# Sheet1.net
KiCad netlist of a schematic drawn in Altium Designer
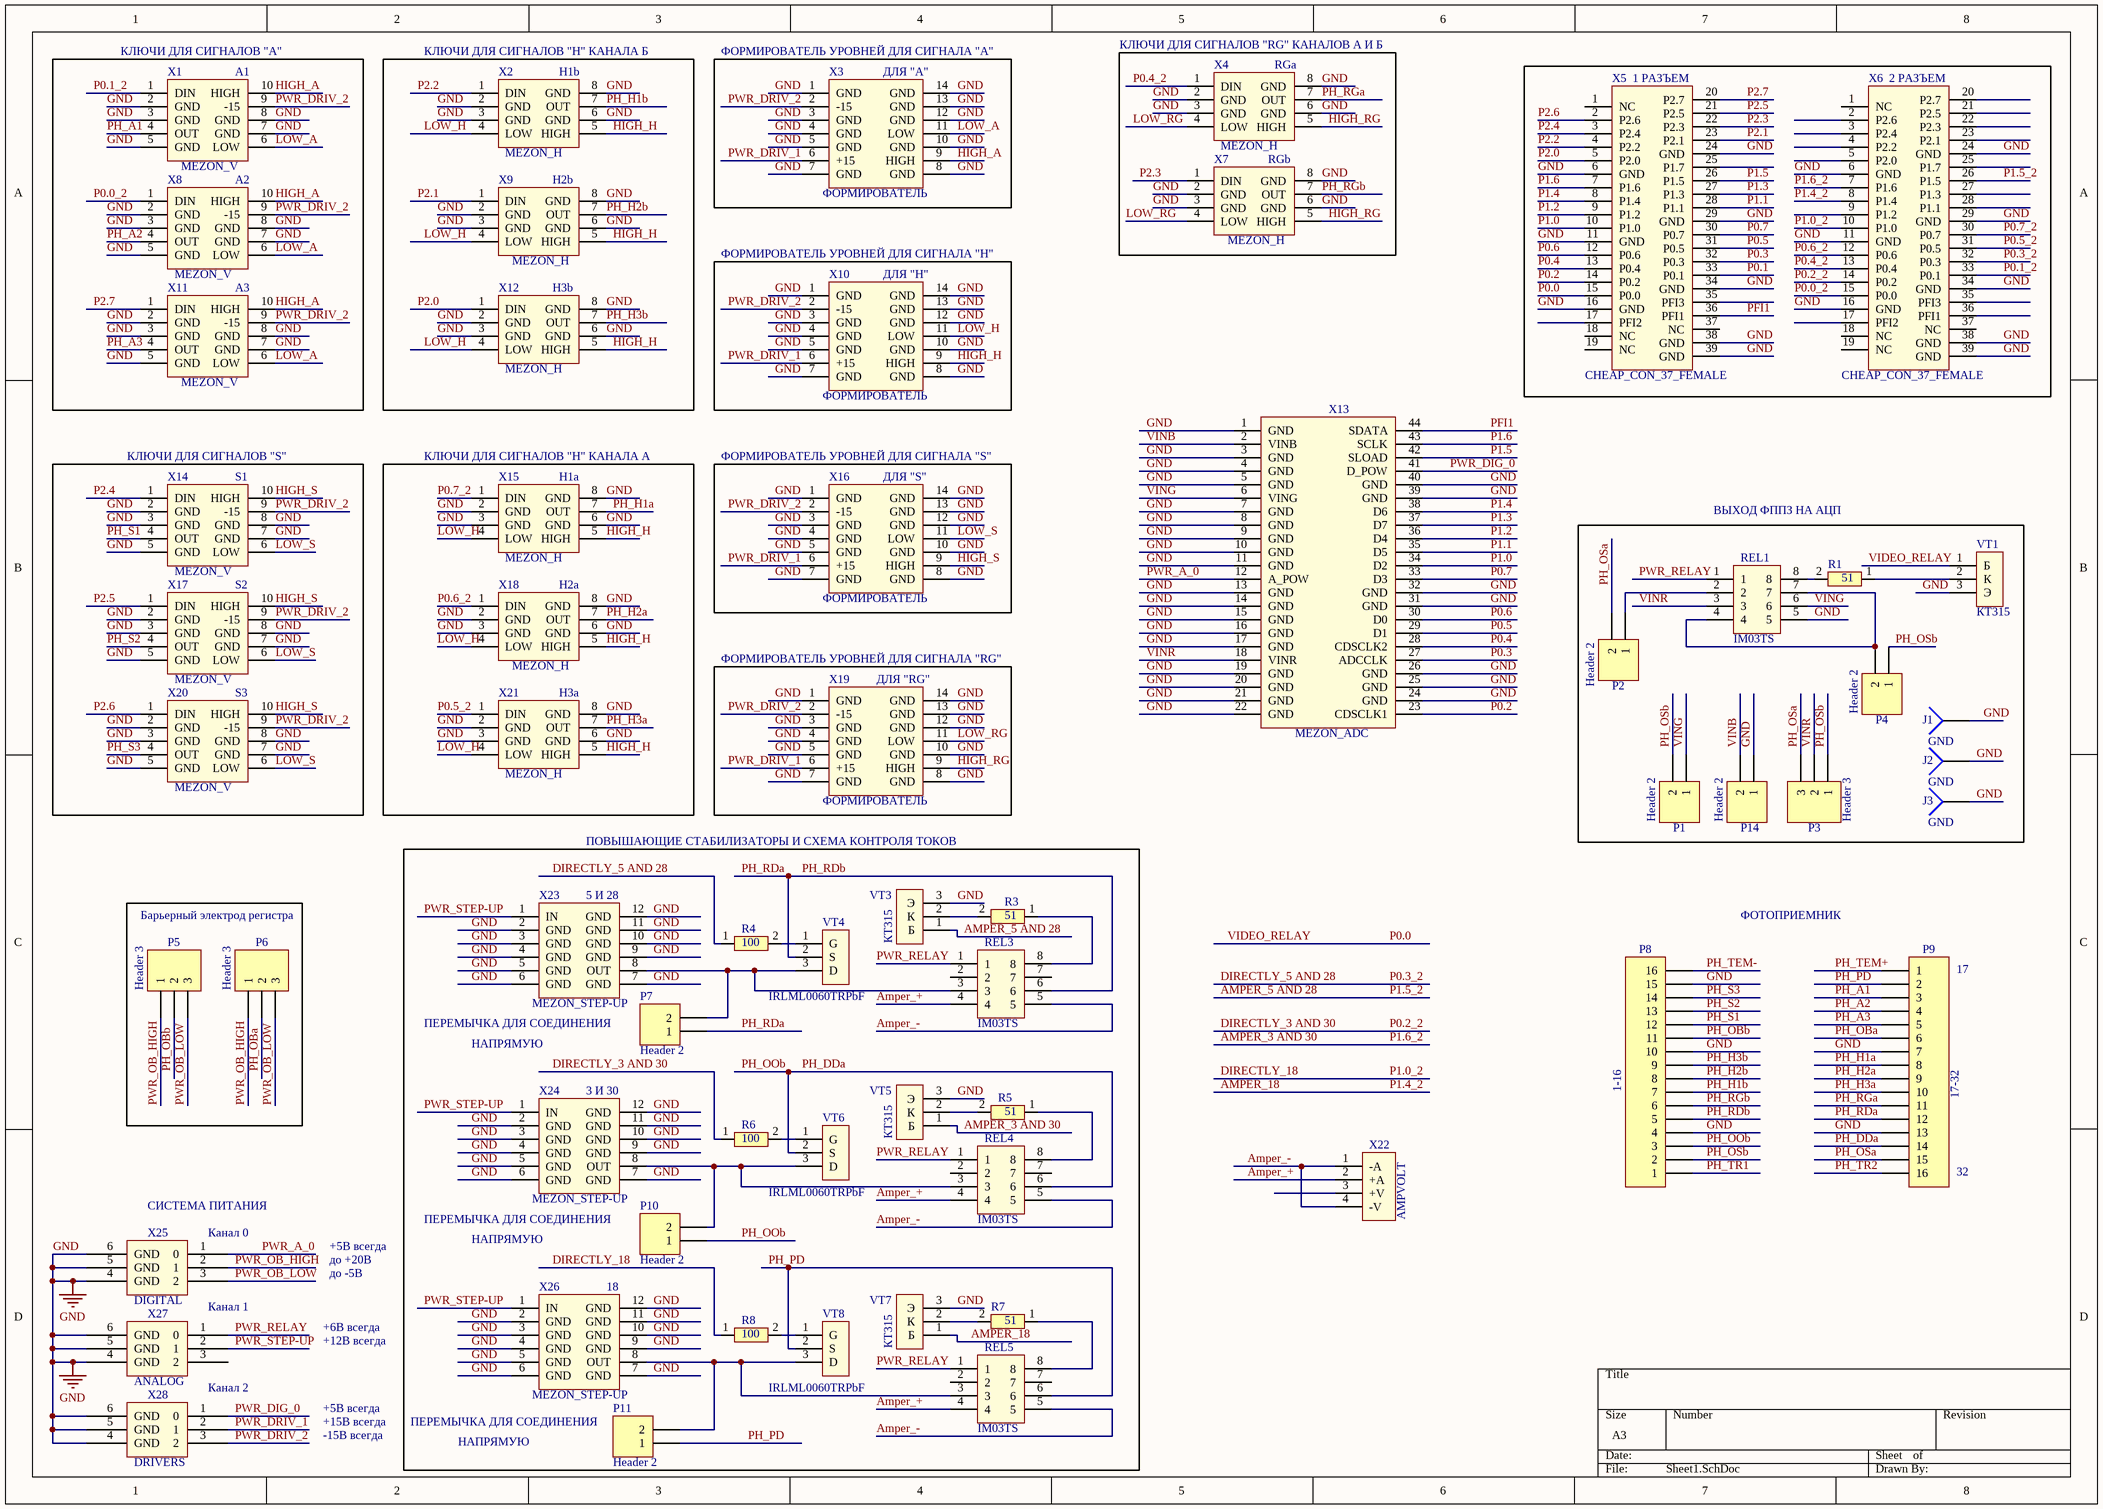
[diagram p0: Sheet1.SchDoc]

(export (version "E")
  (design (tool "Eeschema 10.0.6"))
  (components
    (comp (ref "J1")
      (value "GND")
      (footprint "PIN1")
      (description "Socket")
      (fields (field (name "PUBLISHER") "Altium Limited"))
      (libsource (lib "Miscellaneous Connectors") (part "Socket"))
    )
    (comp (ref "J2")
      (value "GND")
      (footprint "PIN1")
      (description "Socket")
      (fields (field (name "PUBLISHER") "Altium Limited"))
      (libsource (lib "Miscellaneous Connectors") (part "Socket"))
    )
    (comp (ref "J3")
      (value "GND")
      (footprint "PIN1")
      (description "Socket")
      (fields (field (name "PUBLISHER") "Altium Limited"))
      (libsource (lib "Miscellaneous Connectors") (part "Socket"))
    )
    (comp (ref "P1")
      (value "Header 2")
      (footprint "HDR1X2")
      (description "Header, 2-Pin")
      (fields (field (name "PUBLISHER") "Altium Limited"))
      (libsource (lib "Miscellaneous Connectors") (part "Header 2"))
    )
    (comp (ref "P2")
      (value "Header 2")
      (footprint "HDR1X2")
      (description "Header, 2-Pin")
      (fields (field (name "PUBLISHER") "Altium Limited"))
      (libsource (lib "Miscellaneous Connectors") (part "Header 2"))
    )
    (comp (ref "P3")
      (value "Header 3")
      (footprint "HDR1X3")
      (description "Header, 3-Pin")
      (fields (field (name "PUBLISHER") "Altium Limited"))
      (libsource (lib "") (part "Header 3_1"))
    )
    (comp (ref "P4")
      (value "Header 2")
      (footprint "HDR1X2")
      (description "Header, 2-Pin")
      (fields (field (name "PUBLISHER") "Altium Limited"))
      (libsource (lib "Miscellaneous Connectors") (part "Header 2"))
    )
    (comp (ref "P5")
      (value "Header 3")
      (footprint "HDR1X3")
      (description "Header, 3-Pin")
      (fields (field (name "PUBLISHER") "Altium Limited"))
      (libsource (lib "Miscellaneous Connectors") (part "Header 3"))
    )
    (comp (ref "P6")
      (value "Header 3")
      (footprint "HDR1X3")
      (description "Header, 3-Pin")
      (fields (field (name "PUBLISHER") "Altium Limited"))
      (libsource (lib "Miscellaneous Connectors") (part "Header 3"))
    )
    (comp (ref "P7")
      (value "Header 2")
      (footprint "HDR1X2")
      (description "Header, 2-Pin")
      (fields (field (name "PUBLISHER") "Altium Limited"))
      (libsource (lib "") (part "Header 2_1"))
    )
    (comp (ref "P8")
      (value "1-16")
      (footprint "HDR1X16")
      (description "Header, 16-Pin")
      (fields (field (name "PUBLISHER") "Altium Limited"))
      (libsource (lib "") (part "Header 16_1"))
    )
    (comp (ref "P9")
      (value "17-32")
      (footprint "HDR1X16")
      (description "Header, 16-Pin")
      (fields (field (name "PUBLISHER") "Altium Limited"))
      (libsource (lib "Miscellaneous Connectors") (part "Header 16"))
    )
    (comp (ref "P10")
      (value "Header 2")
      (footprint "HDR1X2")
      (description "Header, 2-Pin")
      (fields (field (name "PUBLISHER") "Altium Limited"))
      (libsource (lib "") (part "Header 2_1"))
    )
    (comp (ref "P11")
      (value "Header 2")
      (footprint "HDR1X2")
      (description "Header, 2-Pin")
      (fields (field (name "PUBLISHER") "Altium Limited"))
      (libsource (lib "") (part "Header 2_1"))
    )
    (comp (ref "P14")
      (value "Header 2")
      (footprint "HDR1X2")
      (description "Header, 2-Pin")
      (fields (field (name "PUBLISHER") "Altium Limited"))
      (libsource (lib "Miscellaneous Connectors") (part "Header 2"))
    )
    (comp (ref "R1") (value "51") (footprint "RES") (libsource (lib "Schlib") (part "RES")))
    (comp (ref "R3") (value "51") (footprint "RES") (libsource (lib "Schlib") (part "RES")))
    (comp (ref "R4") (value "100") (footprint "RES") (libsource (lib "") (part "RES_1")))
    (comp (ref "R5") (value "51") (footprint "RES") (libsource (lib "Schlib") (part "RES")))
    (comp (ref "R6") (value "100") (footprint "RES") (libsource (lib "") (part "RES_1")))
    (comp (ref "R7") (value "51") (footprint "RES") (libsource (lib "Schlib") (part "RES")))
    (comp (ref "R8") (value "100") (footprint "RES") (libsource (lib "") (part "RES_1")))
    (comp (ref "REL1") (value "IM03TS") (footprint "IM03TS") (libsource (lib "Schlib") (part "IM03TS")))
    (comp (ref "REL3") (value "IM03TS") (footprint "IM03TS") (libsource (lib "Schlib") (part "IM03TS")))
    (comp (ref "REL4") (value "IM03TS") (footprint "IM03TS") (libsource (lib "Schlib") (part "IM03TS")))
    (comp (ref "REL5") (value "IM03TS") (footprint "IM03TS") (libsource (lib "Schlib") (part "IM03TS")))
    (comp (ref "VT1") (value "КТ315") (footprint "KT315") (libsource (lib "") (part "КТ315_1")))
    (comp (ref "VT3") (value "КТ315") (footprint "KT315") (libsource (lib "Schlib") (part "КТ315")))
    (comp (ref "VT4")
      (value "IRLML0060TRPbF")
      (footprint "SOT23-BEC_MMBT3640*(Primary)")
      (libsource (lib "Schlib") (part "IRLML0060TRPbF"))
    )
    (comp (ref "VT5") (value "КТ315") (footprint "KT315") (libsource (lib "Schlib") (part "КТ315")))
    (comp (ref "VT6")
      (value "IRLML0060TRPbF")
      (footprint "SOT23-BEC_MMBT3640*(Primary)")
      (libsource (lib "Schlib") (part "IRLML0060TRPbF"))
    )
    (comp (ref "VT7") (value "КТ315") (footprint "KT315") (libsource (lib "Schlib") (part "КТ315")))
    (comp (ref "VT8")
      (value "IRLML0060TRPbF")
      (footprint "SOT23-BEC_MMBT3640*(Primary)")
      (libsource (lib "Schlib") (part "IRLML0060TRPbF"))
    )
    (comp (ref "X1") (value "MEZON_V") (footprint "MEZON_V") (libsource (lib "Schlib") (part "MEZON_V")))
    (comp (ref "X2") (value "MEZON_H") (footprint "MEZON_H") (libsource (lib "Schlib") (part "MEZON_H")))
    (comp (ref "X3")
      (value "ФОРМИРОВАТЕЛЬ")
      (footprint "MEZON_V+H")
      (libsource (lib "Schlib") (part "MEZON_V+H"))
    )
    (comp (ref "X4") (value "MEZON_H") (footprint "MEZON_H") (libsource (lib "Schlib") (part "MEZON_H")))
    (comp (ref "X5")
      (value "CHEAP_CON_37_FEMALE")
      (footprint "CHEAP_CONN_FEMALE")
      (libsource (lib "Schlib") (part "CHEAP_CON_37_FEMALE"))
    )
    (comp (ref "X6")
      (value "CHEAP_CON_37_FEMALE")
      (footprint "CHEAP_CONN_FEMALE")
      (libsource (lib "Schlib") (part "CHEAP_CON_37_FEMALE"))
    )
    (comp (ref "X7") (value "MEZON_H") (footprint "MEZON_H") (libsource (lib "Schlib") (part "MEZON_H")))
    (comp (ref "X8") (value "MEZON_V") (footprint "MEZON_V") (libsource (lib "Schlib") (part "MEZON_V")))
    (comp (ref "X9") (value "MEZON_H") (footprint "MEZON_H") (libsource (lib "Schlib") (part "MEZON_H")))
    (comp (ref "X10")
      (value "ФОРМИРОВАТЕЛЬ")
      (footprint "MEZON_V+H")
      (libsource (lib "Schlib") (part "MEZON_V+H"))
    )
    (comp (ref "X11") (value "MEZON_V") (footprint "MEZON_V") (libsource (lib "Schlib") (part "MEZON_V")))
    (comp (ref "X12") (value "MEZON_H") (footprint "MEZON_H") (libsource (lib "Schlib") (part "MEZON_H")))
    (comp (ref "X13")
      (value "MEZON_ADC")
      (footprint "MEZON_ADC")
      (libsource (lib "Schlib") (part "MEZON_ADC"))
    )
    (comp (ref "X14") (value "MEZON_V") (footprint "MEZON_V") (libsource (lib "Schlib") (part "MEZON_V")))
    (comp (ref "X15") (value "MEZON_H") (footprint "MEZON_H") (libsource (lib "Schlib") (part "MEZON_H")))
    (comp (ref "X16")
      (value "ФОРМИРОВАТЕЛЬ")
      (footprint "MEZON_V+H")
      (libsource (lib "Schlib") (part "MEZON_V+H"))
    )
    (comp (ref "X17") (value "MEZON_V") (footprint "MEZON_V") (libsource (lib "Schlib") (part "MEZON_V")))
    (comp (ref "X18") (value "MEZON_H") (footprint "MEZON_H") (libsource (lib "Schlib") (part "MEZON_H")))
    (comp (ref "X19")
      (value "ФОРМИРОВАТЕЛЬ")
      (footprint "MEZON_V+H")
      (libsource (lib "Schlib") (part "MEZON_V+H"))
    )
    (comp (ref "X20") (value "MEZON_V") (footprint "MEZON_V") (libsource (lib "Schlib") (part "MEZON_V")))
    (comp (ref "X21") (value "MEZON_H") (footprint "MEZON_H") (libsource (lib "Schlib") (part "MEZON_H")))
    (comp (ref "X22")
      (value "AMPVOLT")
      (footprint "AMP_VOLTMETER")
      (libsource (lib "Schlib") (part "AMP_VOLTMETER"))
    )
    (comp (ref "X23")
      (value "MEZON_STEP-UP")
      (footprint "MEZON_STEP-UP")
      (libsource (lib "Schlib") (part "MEZON_STEP-UP"))
    )
    (comp (ref "X24")
      (value "MEZON_STEP-UP")
      (footprint "MEZON_STEP-UP")
      (libsource (lib "Schlib") (part "MEZON_STEP-UP"))
    )
    (comp (ref "X25") (value "DIGITAL") (footprint "POWER") (libsource (lib "Schlib") (part "POWER")))
    (comp (ref "X26")
      (value "MEZON_STEP-UP")
      (footprint "MEZON_STEP-UP")
      (libsource (lib "Schlib") (part "MEZON_STEP-UP"))
    )
    (comp (ref "X27") (value "ANALOG") (footprint "POWER") (libsource (lib "Schlib") (part "POWER")))
    (comp (ref "X28") (value "DRIVERS") (footprint "POWER") (libsource (lib "Schlib") (part "POWER")))
  )
  (nets
    (net (code "1") (name "/AMPER_3 AND 30") (class "Default")
      (node (ref "VT5") (pin "1") (pinfunction "Б_1") (pintype "passive"))
      (node (ref "X6") (pin "7") (pinfunction "P1.6_7") (pintype "passive"))
    )
    (net (code "2") (name "/AMPER_5 AND 28") (class "Default")
      (node (ref "VT3") (pin "1") (pinfunction "Б_1") (pintype "passive"))
      (node (ref "X6") (pin "26") (pinfunction "P1.5_26") (pintype "passive"))
    )
    (net (code "3") (name "/AMPER_18") (class "Default")
      (node (ref "VT7") (pin "1") (pinfunction "Б_1") (pintype "passive"))
      (node (ref "X6") (pin "8") (pinfunction "P1.4_8") (pintype "passive"))
    )
    (net (code "4") (name "/Amper_+") (class "Default")
      (node (ref "REL3") (pin "4") (pinfunction "4_4") (pintype "passive"))
      (node (ref "REL4") (pin "4") (pinfunction "4_4") (pintype "passive"))
      (node (ref "REL5") (pin "4") (pinfunction "4_4") (pintype "passive"))
      (node (ref "X22") (pin "2") (pinfunction "+A_2") (pintype "passive"))
    )
    (net (code "5") (name "/Amper_-") (class "Default")
      (node (ref "REL3") (pin "5") (pinfunction "5_5") (pintype "passive"))
      (node (ref "REL4") (pin "5") (pinfunction "5_5") (pintype "passive"))
      (node (ref "REL5") (pin "5") (pinfunction "5_5") (pintype "passive"))
      (node (ref "X22") (pin "1") (pinfunction "-A_1") (pintype "passive"))
      (node (ref "X22") (pin "4") (pinfunction "-V_4") (pintype "passive"))
    )
    (net (code "6") (name "/DIRECTLY_3 AND 30") (class "Default")
      (node (ref "R6") (pin "1") (pinfunction "1_1") (pintype "passive"))
      (node (ref "X6") (pin "14") (pinfunction "P0.2_14") (pintype "passive"))
    )
    (net (code "7") (name "/DIRECTLY_5 AND 28") (class "Default")
      (node (ref "R4") (pin "1") (pinfunction "1_1") (pintype "passive"))
      (node (ref "X6") (pin "32") (pinfunction "P0.3_32") (pintype "passive"))
    )
    (net (code "8") (name "/DIRECTLY_18") (class "Default")
      (node (ref "R8") (pin "1") (pinfunction "1_1") (pintype "passive"))
      (node (ref "X6") (pin "10") (pinfunction "P1.0_10") (pintype "passive"))
    )
    (net (code "9") (name "/HIGH_A") (class "Default")
      (node (ref "X1") (pin "10") (pinfunction "HIGH_10") (pintype "passive"))
      (node (ref "X11") (pin "10") (pinfunction "HIGH_10") (pintype "passive"))
      (node (ref "X3") (pin "9") (pinfunction "HIGH_9") (pintype "passive"))
      (node (ref "X8") (pin "10") (pinfunction "HIGH_10") (pintype "passive"))
    )
    (net (code "10") (name "/HIGH_H") (class "Default")
      (node (ref "X10") (pin "9") (pinfunction "HIGH_9") (pintype "passive"))
      (node (ref "X12") (pin "5") (pinfunction "HIGH_5") (pintype "passive"))
      (node (ref "X15") (pin "5") (pinfunction "HIGH_5") (pintype "passive"))
      (node (ref "X18") (pin "5") (pinfunction "HIGH_5") (pintype "passive"))
      (node (ref "X2") (pin "5") (pinfunction "HIGH_5") (pintype "passive"))
      (node (ref "X21") (pin "5") (pinfunction "HIGH_5") (pintype "passive"))
      (node (ref "X9") (pin "5") (pinfunction "HIGH_5") (pintype "passive"))
    )
    (net (code "11") (name "/HIGH_RG") (class "Default")
      (node (ref "X19") (pin "9") (pinfunction "HIGH_9") (pintype "passive"))
      (node (ref "X4") (pin "5") (pinfunction "HIGH_5") (pintype "passive"))
      (node (ref "X7") (pin "5") (pinfunction "HIGH_5") (pintype "passive"))
    )
    (net (code "12") (name "/HIGH_S") (class "Default")
      (node (ref "X14") (pin "10") (pinfunction "HIGH_10") (pintype "passive"))
      (node (ref "X16") (pin "9") (pinfunction "HIGH_9") (pintype "passive"))
      (node (ref "X17") (pin "10") (pinfunction "HIGH_10") (pintype "passive"))
      (node (ref "X20") (pin "10") (pinfunction "HIGH_10") (pintype "passive"))
    )
    (net (code "13") (name "/LOW_A") (class "Default")
      (node (ref "X1") (pin "6") (pinfunction "LOW_6") (pintype "passive"))
      (node (ref "X11") (pin "6") (pinfunction "LOW_6") (pintype "passive"))
      (node (ref "X3") (pin "11") (pinfunction "LOW_11") (pintype "passive"))
      (node (ref "X8") (pin "6") (pinfunction "LOW_6") (pintype "passive"))
    )
    (net (code "14") (name "/LOW_H") (class "Default")
      (node (ref "X10") (pin "11") (pinfunction "LOW_11") (pintype "passive"))
      (node (ref "X12") (pin "4") (pinfunction "LOW_4") (pintype "passive"))
      (node (ref "X15") (pin "4") (pinfunction "LOW_4") (pintype "passive"))
      (node (ref "X18") (pin "4") (pinfunction "LOW_4") (pintype "passive"))
      (node (ref "X2") (pin "4") (pinfunction "LOW_4") (pintype "passive"))
      (node (ref "X21") (pin "4") (pinfunction "LOW_4") (pintype "passive"))
      (node (ref "X9") (pin "4") (pinfunction "LOW_4") (pintype "passive"))
    )
    (net (code "15") (name "/LOW_RG") (class "Default")
      (node (ref "X19") (pin "11") (pinfunction "LOW_11") (pintype "passive"))
      (node (ref "X4") (pin "4") (pinfunction "LOW_4") (pintype "passive"))
      (node (ref "X7") (pin "4") (pinfunction "LOW_4") (pintype "passive"))
    )
    (net (code "16") (name "/LOW_S") (class "Default")
      (node (ref "X14") (pin "6") (pinfunction "LOW_6") (pintype "passive"))
      (node (ref "X16") (pin "11") (pinfunction "LOW_11") (pintype "passive"))
      (node (ref "X17") (pin "6") (pinfunction "LOW_6") (pintype "passive"))
      (node (ref "X20") (pin "6") (pinfunction "LOW_6") (pintype "passive"))
    )
    (net (code "17") (name "/P0.0") (class "Default")
      (node (ref "VT1") (pin "1") (pinfunction "Б_1") (pintype "passive"))
      (node (ref "X5") (pin "15") (pinfunction "P0.0_15") (pintype "passive"))
    )
    (net (code "18") (name "/P0.0_2") (class "Default")
      (node (ref "X6") (pin "15") (pinfunction "P0.0_15") (pintype "passive"))
      (node (ref "X8") (pin "1") (pinfunction "DIN_1") (pintype "passive"))
    )
    (net (code "19") (name "/P0.1") (class "Default")
      (node (ref "X5") (pin "33") (pinfunction "P0.1_33") (pintype "passive"))
    )
    (net (code "20") (name "/P0.1_2") (class "Default")
      (node (ref "X1") (pin "1") (pinfunction "DIN_1") (pintype "passive"))
      (node (ref "X6") (pin "33") (pinfunction "P0.1_33") (pintype "passive"))
    )
    (net (code "21") (name "/P0.2") (class "Default")
      (node (ref "X13") (pin "23") (pinfunction "CDSCLK1_23") (pintype "passive"))
      (node (ref "X5") (pin "14") (pinfunction "P0.2_14") (pintype "passive"))
    )
    (net (code "22") (name "/P0.3") (class "Default")
      (node (ref "X13") (pin "27") (pinfunction "ADCCLK_27") (pintype "passive"))
      (node (ref "X5") (pin "32") (pinfunction "P0.3_32") (pintype "passive"))
    )
    (net (code "23") (name "/P0.4") (class "Default")
      (node (ref "X13") (pin "28") (pinfunction "CDSCLK2_28") (pintype "passive"))
      (node (ref "X5") (pin "13") (pinfunction "P0.4_13") (pintype "passive"))
    )
    (net (code "24") (name "/P0.4_2") (class "Default")
      (node (ref "X4") (pin "1") (pinfunction "DIN_1") (pintype "passive"))
      (node (ref "X6") (pin "13") (pinfunction "P0.4_13") (pintype "passive"))
    )
    (net (code "25") (name "/P0.5") (class "Default")
      (node (ref "X13") (pin "29") (pinfunction "D1_29") (pintype "passive"))
      (node (ref "X5") (pin "31") (pinfunction "P0.5_31") (pintype "passive"))
    )
    (net (code "26") (name "/P0.5_2") (class "Default")
      (node (ref "X21") (pin "1") (pinfunction "DIN_1") (pintype "passive"))
      (node (ref "X6") (pin "31") (pinfunction "P0.5_31") (pintype "passive"))
    )
    (net (code "27") (name "/P0.6") (class "Default")
      (node (ref "X13") (pin "30") (pinfunction "D0_30") (pintype "passive"))
      (node (ref "X5") (pin "12") (pinfunction "P0.6_12") (pintype "passive"))
    )
    (net (code "28") (name "/P0.6_2") (class "Default")
      (node (ref "X18") (pin "1") (pinfunction "DIN_1") (pintype "passive"))
      (node (ref "X6") (pin "12") (pinfunction "P0.6_12") (pintype "passive"))
    )
    (net (code "29") (name "/P0.7") (class "Default")
      (node (ref "X13") (pin "33") (pinfunction "D3_33") (pintype "passive"))
      (node (ref "X5") (pin "30") (pinfunction "P0.7_30") (pintype "passive"))
    )
    (net (code "30") (name "/P0.7_2") (class "Default")
      (node (ref "X15") (pin "1") (pinfunction "DIN_1") (pintype "passive"))
      (node (ref "X6") (pin "30") (pinfunction "P0.7_30") (pintype "passive"))
    )
    (net (code "31") (name "/P1.0") (class "Default")
      (node (ref "X13") (pin "34") (pinfunction "D2_34") (pintype "passive"))
      (node (ref "X5") (pin "10") (pinfunction "P1.0_10") (pintype "passive"))
    )
    (net (code "32") (name "/P1.1") (class "Default")
      (node (ref "X13") (pin "35") (pinfunction "D5_35") (pintype "passive"))
      (node (ref "X5") (pin "28") (pinfunction "P1.1_28") (pintype "passive"))
    )
    (net (code "33") (name "/P1.2") (class "Default")
      (node (ref "X13") (pin "36") (pinfunction "D4_36") (pintype "passive"))
      (node (ref "X5") (pin "9") (pinfunction "P1.2_9") (pintype "passive"))
    )
    (net (code "34") (name "/P1.3") (class "Default")
      (node (ref "X13") (pin "37") (pinfunction "D7_37") (pintype "passive"))
      (node (ref "X5") (pin "27") (pinfunction "P1.3_27") (pintype "passive"))
    )
    (net (code "35") (name "/P1.4") (class "Default")
      (node (ref "X13") (pin "38") (pinfunction "D6_38") (pintype "passive"))
      (node (ref "X5") (pin "8") (pinfunction "P1.4_8") (pintype "passive"))
    )
    (net (code "36") (name "/P1.5") (class "Default")
      (node (ref "X13") (pin "42") (pinfunction "SLOAD_42") (pintype "passive"))
      (node (ref "X5") (pin "26") (pinfunction "P1.5_26") (pintype "passive"))
    )
    (net (code "37") (name "/P1.6") (class "Default")
      (node (ref "X13") (pin "43") (pinfunction "SCLK_43") (pintype "passive"))
      (node (ref "X5") (pin "7") (pinfunction "P1.6_7") (pintype "passive"))
    )
    (net (code "38") (name "/P2.0") (class "Default")
      (node (ref "X12") (pin "1") (pinfunction "DIN_1") (pintype "passive"))
      (node (ref "X5") (pin "5") (pinfunction "P2.0_5") (pintype "passive"))
    )
    (net (code "39") (name "/P2.1") (class "Default")
      (node (ref "X5") (pin "23") (pinfunction "P2.1_23") (pintype "passive"))
      (node (ref "X9") (pin "1") (pinfunction "DIN_1") (pintype "passive"))
    )
    (net (code "40") (name "/P2.2") (class "Default")
      (node (ref "X2") (pin "1") (pinfunction "DIN_1") (pintype "passive"))
      (node (ref "X5") (pin "4") (pinfunction "P2.2_4") (pintype "passive"))
    )
    (net (code "41") (name "/P2.3") (class "Default")
      (node (ref "X5") (pin "22") (pinfunction "P2.3_22") (pintype "passive"))
      (node (ref "X7") (pin "1") (pinfunction "DIN_1") (pintype "passive"))
    )
    (net (code "42") (name "/P2.4") (class "Default")
      (node (ref "X14") (pin "1") (pinfunction "DIN_1") (pintype "passive"))
      (node (ref "X5") (pin "3") (pinfunction "P2.4_3") (pintype "passive"))
    )
    (net (code "43") (name "/P2.5") (class "Default")
      (node (ref "X17") (pin "1") (pinfunction "DIN_1") (pintype "passive"))
      (node (ref "X5") (pin "21") (pinfunction "P2.5_21") (pintype "passive"))
    )
    (net (code "44") (name "/P2.6") (class "Default")
      (node (ref "X20") (pin "1") (pinfunction "DIN_1") (pintype "passive"))
      (node (ref "X5") (pin "2") (pinfunction "P2.6_2") (pintype "passive"))
    )
    (net (code "45") (name "/P2.7") (class "Default")
      (node (ref "X11") (pin "1") (pinfunction "DIN_1") (pintype "passive"))
      (node (ref "X5") (pin "20") (pinfunction "P2.7_20") (pintype "passive"))
    )
    (net (code "46") (name "/PFI1") (class "Default")
      (node (ref "X13") (pin "44") (pinfunction "SDATA_44") (pintype "passive"))
      (node (ref "X5") (pin "36") (pinfunction "PFI1_36") (pintype "passive"))
    )
    (net (code "47") (name "/PH_A1") (class "Default")
      (node (ref "P9") (pin "3") (pinfunction "3_3") (pintype "passive"))
      (node (ref "X1") (pin "4") (pinfunction "OUT_4") (pintype "passive"))
    )
    (net (code "48") (name "/PH_A2") (class "Default")
      (node (ref "P9") (pin "4") (pinfunction "4_4") (pintype "passive"))
      (node (ref "X8") (pin "4") (pinfunction "OUT_4") (pintype "passive"))
    )
    (net (code "49") (name "/PH_A3") (class "Default")
      (node (ref "P9") (pin "5") (pinfunction "5_5") (pintype "passive"))
      (node (ref "X11") (pin "4") (pinfunction "OUT_4") (pintype "passive"))
    )
    (net (code "50") (name "/PH_DDa") (class "Default")
      (node (ref "P10") (pin "1") (pinfunction "1_1") (pintype "passive"))
      (node (ref "P8") (pin "3") (pinfunction "3_3") (pintype "passive"))
      (node (ref "P9") (pin "14") (pinfunction "14_14") (pintype "passive"))
      (node (ref "REL4") (pin "6") (pinfunction "6_6") (pintype "passive"))
      (node (ref "VT6") (pin "2") (pinfunction "S_2") (pintype "passive"))
    )
    (net (code "51") (name "/PH_H1a") (class "Default")
      (node (ref "P9") (pin "8") (pinfunction "8_8") (pintype "passive"))
      (node (ref "X15") (pin "7") (pinfunction "OUT_7") (pintype "passive"))
    )
    (net (code "52") (name "/PH_H1b") (class "Default")
      (node (ref "P8") (pin "7") (pinfunction "7_7") (pintype "passive"))
      (node (ref "X2") (pin "7") (pinfunction "OUT_7") (pintype "passive"))
    )
    (net (code "53") (name "/PH_H2a") (class "Default")
      (node (ref "P9") (pin "9") (pinfunction "9_9") (pintype "passive"))
      (node (ref "X18") (pin "7") (pinfunction "OUT_7") (pintype "passive"))
    )
    (net (code "54") (name "/PH_H2b") (class "Default")
      (node (ref "P8") (pin "8") (pinfunction "8_8") (pintype "passive"))
      (node (ref "X9") (pin "7") (pinfunction "OUT_7") (pintype "passive"))
    )
    (net (code "55") (name "/PH_H3a") (class "Default")
      (node (ref "P9") (pin "10") (pinfunction "10_10") (pintype "passive"))
      (node (ref "X21") (pin "7") (pinfunction "OUT_7") (pintype "passive"))
    )
    (net (code "56") (name "/PH_H3b") (class "Default")
      (node (ref "P8") (pin "9") (pinfunction "9_9") (pintype "passive"))
      (node (ref "X12") (pin "7") (pinfunction "OUT_7") (pintype "passive"))
    )
    (net (code "57") (name "/PH_OBa") (class "Default")
      (node (ref "P6") (pin "2") (pinfunction "2_2") (pintype "passive"))
      (node (ref "P9") (pin "6") (pinfunction "6_6") (pintype "passive"))
    )
    (net (code "58") (name "/PH_OBb") (class "Default")
      (node (ref "P5") (pin "2") (pinfunction "2_2") (pintype "passive"))
      (node (ref "P8") (pin "11") (pinfunction "11_11") (pintype "passive"))
    )
    (net (code "59") (name "/PH_OSa") (class "Default")
      (node (ref "P2") (pin "2") (pinfunction "2_2") (pintype "passive"))
      (node (ref "P3") (pin "3") (pinfunction "3_3") (pintype "passive"))
      (node (ref "P9") (pin "15") (pinfunction "15_15") (pintype "passive"))
    )
    (net (code "60") (name "/PH_OSb") (class "Default")
      (node (ref "P1") (pin "2") (pinfunction "2_2") (pintype "passive"))
      (node (ref "P3") (pin "1") (pinfunction "1_1") (pintype "passive"))
      (node (ref "P4") (pin "1") (pinfunction "1_1") (pintype "passive"))
      (node (ref "P8") (pin "2") (pinfunction "2_2") (pintype "passive"))
    )
    (net (code "61") (name "/PH_PD") (class "Default")
      (node (ref "P11") (pin "1") (pinfunction "1_1") (pintype "passive"))
      (node (ref "P9") (pin "2") (pinfunction "2_2") (pintype "passive"))
      (node (ref "REL5") (pin "6") (pinfunction "6_6") (pintype "passive"))
      (node (ref "VT8") (pin "2") (pinfunction "S_2") (pintype "passive"))
    )
    (net (code "62") (name "/PH_RDa") (class "Default")
      (node (ref "P7") (pin "1") (pinfunction "1_1") (pintype "passive"))
      (node (ref "P8") (pin "5") (pinfunction "5_5") (pintype "passive"))
      (node (ref "P9") (pin "12") (pinfunction "12_12") (pintype "passive"))
      (node (ref "REL3") (pin "6") (pinfunction "6_6") (pintype "passive"))
      (node (ref "VT4") (pin "2") (pinfunction "S_2") (pintype "passive"))
    )
    (net (code "63") (name "/PH_RGa") (class "Default")
      (node (ref "P9") (pin "11") (pinfunction "11_11") (pintype "passive"))
      (node (ref "X4") (pin "7") (pinfunction "OUT_7") (pintype "passive"))
    )
    (net (code "64") (name "/PH_RGb") (class "Default")
      (node (ref "P8") (pin "6") (pinfunction "6_6") (pintype "passive"))
      (node (ref "X7") (pin "7") (pinfunction "OUT_7") (pintype "passive"))
    )
    (net (code "65") (name "/PH_S1") (class "Default")
      (node (ref "P8") (pin "12") (pinfunction "12_12") (pintype "passive"))
      (node (ref "X14") (pin "4") (pinfunction "OUT_4") (pintype "passive"))
    )
    (net (code "66") (name "/PH_S2") (class "Default")
      (node (ref "P8") (pin "13") (pinfunction "13_13") (pintype "passive"))
      (node (ref "X17") (pin "4") (pinfunction "OUT_4") (pintype "passive"))
    )
    (net (code "67") (name "/PH_S3") (class "Default")
      (node (ref "P8") (pin "14") (pinfunction "14_14") (pintype "passive"))
      (node (ref "X20") (pin "4") (pinfunction "OUT_4") (pintype "passive"))
    )
    (net (code "68") (name "/PH_TEM+") (class "Default")
      (node (ref "P9") (pin "1") (pinfunction "1_1") (pintype "passive"))
    )
    (net (code "69") (name "/PH_TEM-") (class "Default")
      (node (ref "P8") (pin "16") (pinfunction "16_16") (pintype "passive"))
    )
    (net (code "70") (name "/PH_TR1") (class "Default")
      (node (ref "P8") (pin "1") (pinfunction "1_1") (pintype "passive"))
    )
    (net (code "71") (name "/PH_TR2") (class "Default")
      (node (ref "P9") (pin "16") (pinfunction "16_16") (pintype "passive"))
    )
    (net (code "72") (name "/PWR_A_0") (class "Default")
      (node (ref "X13") (pin "12") (pinfunction "A_POW_12") (pintype "passive"))
      (node (ref "X25") (pin "1") (pinfunction "0_1") (pintype "passive"))
    )
    (net (code "73") (name "/PWR_DIG_0") (class "Default")
      (node (ref "X13") (pin "41") (pinfunction "D_POW_41") (pintype "passive"))
      (node (ref "X28") (pin "1") (pinfunction "0_1") (pintype "passive"))
    )
    (net (code "74") (name "/PWR_DRIV_1") (class "Default")
      (node (ref "X10") (pin "6") (pinfunction "+15_6") (pintype "passive"))
      (node (ref "X16") (pin "6") (pinfunction "+15_6") (pintype "passive"))
      (node (ref "X19") (pin "6") (pinfunction "+15_6") (pintype "passive"))
      (node (ref "X28") (pin "2") (pinfunction "1_2") (pintype "passive"))
      (node (ref "X3") (pin "6") (pinfunction "+15_6") (pintype "passive"))
    )
    (net (code "75") (name "/PWR_DRIV_2") (class "Default")
      (node (ref "X1") (pin "9") (pinfunction "-15_9") (pintype "passive"))
      (node (ref "X10") (pin "2") (pinfunction "-15_2") (pintype "passive"))
      (node (ref "X11") (pin "9") (pinfunction "-15_9") (pintype "passive"))
      (node (ref "X14") (pin "9") (pinfunction "-15_9") (pintype "passive"))
      (node (ref "X16") (pin "2") (pinfunction "-15_2") (pintype "passive"))
      (node (ref "X17") (pin "9") (pinfunction "-15_9") (pintype "passive"))
      (node (ref "X19") (pin "2") (pinfunction "-15_2") (pintype "passive"))
      (node (ref "X20") (pin "9") (pinfunction "-15_9") (pintype "passive"))
      (node (ref "X28") (pin "3") (pinfunction "2_3") (pintype "passive"))
      (node (ref "X3") (pin "2") (pinfunction "-15_2") (pintype "passive"))
      (node (ref "X8") (pin "9") (pinfunction "-15_9") (pintype "passive"))
    )
    (net (code "76") (name "/PWR_OB_HIGH") (class "Default")
      (node (ref "P5") (pin "1") (pinfunction "1_1") (pintype "passive"))
      (node (ref "P6") (pin "1") (pinfunction "1_1") (pintype "passive"))
      (node (ref "X25") (pin "2") (pinfunction "1_2") (pintype "passive"))
    )
    (net (code "77") (name "/PWR_OB_LOW") (class "Default")
      (node (ref "P5") (pin "3") (pinfunction "3_3") (pintype "passive"))
      (node (ref "P6") (pin "3") (pinfunction "3_3") (pintype "passive"))
      (node (ref "X25") (pin "3") (pinfunction "2_3") (pintype "passive"))
    )
    (net (code "78") (name "/PWR_RELAY") (class "Default")
      (node (ref "REL1") (pin "1") (pinfunction "1_1") (pintype "passive"))
      (node (ref "REL3") (pin "1") (pinfunction "1_1") (pintype "passive"))
      (node (ref "REL4") (pin "1") (pinfunction "1_1") (pintype "passive"))
      (node (ref "REL5") (pin "1") (pinfunction "1_1") (pintype "passive"))
      (node (ref "X27") (pin "1") (pinfunction "0_1") (pintype "passive"))
    )
    (net (code "79") (name "/PWR_STEP-UP") (class "Default")
      (node (ref "X23") (pin "1") (pinfunction "IN_1") (pintype "passive"))
      (node (ref "X24") (pin "1") (pinfunction "IN_1") (pintype "passive"))
      (node (ref "X26") (pin "1") (pinfunction "IN_1") (pintype "passive"))
      (node (ref "X27") (pin "2") (pinfunction "1_2") (pintype "passive"))
    )
    (net (code "80") (name "/VINB") (class "Default")
      (node (ref "P14") (pin "2") (pinfunction "2_2") (pintype "passive"))
      (node (ref "X13") (pin "2") (pinfunction "VINB_2") (pintype "passive"))
    )
    (net (code "81") (name "/VING") (class "Default")
      (node (ref "P1") (pin "1") (pinfunction "1_1") (pintype "passive"))
      (node (ref "REL1") (pin "6") (pinfunction "6_6") (pintype "passive"))
      (node (ref "X13") (pin "6") (pinfunction "VING_6") (pintype "passive"))
    )
    (net (code "82") (name "/VINR") (class "Default")
      (node (ref "P3") (pin "2") (pinfunction "2_2") (pintype "passive"))
      (node (ref "REL1") (pin "3") (pinfunction "3_3") (pintype "passive"))
      (node (ref "X13") (pin "18") (pinfunction "VINR_18") (pintype "passive"))
    )
    (net (code "83") (name "GND") (class "Default")
      (node (ref "J1") (pin "1") (pinfunction "1_1") (pintype "passive"))
      (node (ref "J2") (pin "1") (pinfunction "1_1") (pintype "passive"))
      (node (ref "J3") (pin "1") (pinfunction "1_1") (pintype "passive"))
      (node (ref "P14") (pin "1") (pinfunction "1_1") (pintype "passive"))
      (node (ref "P8") (pin "10") (pinfunction "10_10") (pintype "passive"))
      (node (ref "P8") (pin "15") (pinfunction "15_15") (pintype "passive"))
      (node (ref "P8") (pin "4") (pinfunction "4_4") (pintype "passive"))
      (node (ref "P9") (pin "13") (pinfunction "13_13") (pintype "passive"))
      (node (ref "P9") (pin "7") (pinfunction "7_7") (pintype "passive"))
      (node (ref "REL1") (pin "5") (pinfunction "5_5") (pintype "passive"))
      (node (ref "VT1") (pin "3") (pinfunction "Э_3") (pintype "passive"))
      (node (ref "VT3") (pin "3") (pinfunction "Э_3") (pintype "passive"))
      (node (ref "VT5") (pin "3") (pinfunction "Э_3") (pintype "passive"))
      (node (ref "VT7") (pin "3") (pinfunction "Э_3") (pintype "passive"))
      (node (ref "X1") (pin "2") (pinfunction "GND_2") (pintype "passive"))
      (node (ref "X1") (pin "3") (pinfunction "GND_3") (pintype "passive"))
      (node (ref "X1") (pin "5") (pinfunction "GND_5") (pintype "passive"))
      (node (ref "X1") (pin "7") (pinfunction "GND_7") (pintype "passive"))
      (node (ref "X1") (pin "8") (pinfunction "GND_8") (pintype "passive"))
      (node (ref "X10") (pin "1") (pinfunction "GND_1") (pintype "passive"))
      (node (ref "X10") (pin "10") (pinfunction "GND_10") (pintype "passive"))
      (node (ref "X10") (pin "12") (pinfunction "GND_12") (pintype "passive"))
      (node (ref "X10") (pin "13") (pinfunction "GND_13") (pintype "passive"))
      (node (ref "X10") (pin "14") (pinfunction "GND_14") (pintype "passive"))
      (node (ref "X10") (pin "3") (pinfunction "GND_3") (pintype "passive"))
      (node (ref "X10") (pin "4") (pinfunction "GND_4") (pintype "passive"))
      (node (ref "X10") (pin "5") (pinfunction "GND_5") (pintype "passive"))
      (node (ref "X10") (pin "7") (pinfunction "GND_7") (pintype "passive"))
      (node (ref "X10") (pin "8") (pinfunction "GND_8") (pintype "passive"))
      (node (ref "X11") (pin "2") (pinfunction "GND_2") (pintype "passive"))
      (node (ref "X11") (pin "3") (pinfunction "GND_3") (pintype "passive"))
      (node (ref "X11") (pin "5") (pinfunction "GND_5") (pintype "passive"))
      (node (ref "X11") (pin "7") (pinfunction "GND_7") (pintype "passive"))
      (node (ref "X11") (pin "8") (pinfunction "GND_8") (pintype "passive"))
      (node (ref "X12") (pin "2") (pinfunction "GND_2") (pintype "passive"))
      (node (ref "X12") (pin "3") (pinfunction "GND_3") (pintype "passive"))
      (node (ref "X12") (pin "6") (pinfunction "GND_6") (pintype "passive"))
      (node (ref "X12") (pin "8") (pinfunction "GND_8") (pintype "passive"))
      (node (ref "X13") (pin "1") (pinfunction "GND_1") (pintype "passive"))
      (node (ref "X13") (pin "10") (pinfunction "GND_10") (pintype "passive"))
      (node (ref "X13") (pin "11") (pinfunction "GND_11") (pintype "passive"))
      (node (ref "X13") (pin "13") (pinfunction "GND_13") (pintype "passive"))
      (node (ref "X13") (pin "14") (pinfunction "GND_14") (pintype "passive"))
      (node (ref "X13") (pin "15") (pinfunction "GND_15") (pintype "passive"))
      (node (ref "X13") (pin "16") (pinfunction "GND_16") (pintype "passive"))
      (node (ref "X13") (pin "17") (pinfunction "GND_17") (pintype "passive"))
      (node (ref "X13") (pin "19") (pinfunction "GND_19") (pintype "passive"))
      (node (ref "X13") (pin "20") (pinfunction "GND_20") (pintype "passive"))
      (node (ref "X13") (pin "21") (pinfunction "GND_21") (pintype "passive"))
      (node (ref "X13") (pin "22") (pinfunction "GND_22") (pintype "passive"))
      (node (ref "X13") (pin "24") (pinfunction "GND_24") (pintype "passive"))
      (node (ref "X13") (pin "25") (pinfunction "GND_25") (pintype "passive"))
      (node (ref "X13") (pin "26") (pinfunction "GND_26") (pintype "passive"))
      (node (ref "X13") (pin "3") (pinfunction "GND_3") (pintype "passive"))
      (node (ref "X13") (pin "31") (pinfunction "GND_31") (pintype "passive"))
      (node (ref "X13") (pin "32") (pinfunction "GND_32") (pintype "passive"))
      (node (ref "X13") (pin "39") (pinfunction "GND_39") (pintype "passive"))
      (node (ref "X13") (pin "4") (pinfunction "GND_4") (pintype "passive"))
      (node (ref "X13") (pin "40") (pinfunction "GND_40") (pintype "passive"))
      (node (ref "X13") (pin "5") (pinfunction "GND_5") (pintype "passive"))
      (node (ref "X13") (pin "7") (pinfunction "GND_7") (pintype "passive"))
      (node (ref "X13") (pin "8") (pinfunction "GND_8") (pintype "passive"))
      (node (ref "X13") (pin "9") (pinfunction "GND_9") (pintype "passive"))
      (node (ref "X14") (pin "2") (pinfunction "GND_2") (pintype "passive"))
      (node (ref "X14") (pin "3") (pinfunction "GND_3") (pintype "passive"))
      (node (ref "X14") (pin "5") (pinfunction "GND_5") (pintype "passive"))
      (node (ref "X14") (pin "7") (pinfunction "GND_7") (pintype "passive"))
      (node (ref "X14") (pin "8") (pinfunction "GND_8") (pintype "passive"))
      (node (ref "X15") (pin "2") (pinfunction "GND_2") (pintype "passive"))
      (node (ref "X15") (pin "3") (pinfunction "GND_3") (pintype "passive"))
      (node (ref "X15") (pin "6") (pinfunction "GND_6") (pintype "passive"))
      (node (ref "X15") (pin "8") (pinfunction "GND_8") (pintype "passive"))
      (node (ref "X16") (pin "1") (pinfunction "GND_1") (pintype "passive"))
      (node (ref "X16") (pin "10") (pinfunction "GND_10") (pintype "passive"))
      (node (ref "X16") (pin "12") (pinfunction "GND_12") (pintype "passive"))
      (node (ref "X16") (pin "13") (pinfunction "GND_13") (pintype "passive"))
      (node (ref "X16") (pin "14") (pinfunction "GND_14") (pintype "passive"))
      (node (ref "X16") (pin "3") (pinfunction "GND_3") (pintype "passive"))
      (node (ref "X16") (pin "4") (pinfunction "GND_4") (pintype "passive"))
      (node (ref "X16") (pin "5") (pinfunction "GND_5") (pintype "passive"))
      (node (ref "X16") (pin "7") (pinfunction "GND_7") (pintype "passive"))
      (node (ref "X16") (pin "8") (pinfunction "GND_8") (pintype "passive"))
      (node (ref "X17") (pin "2") (pinfunction "GND_2") (pintype "passive"))
      (node (ref "X17") (pin "3") (pinfunction "GND_3") (pintype "passive"))
      (node (ref "X17") (pin "5") (pinfunction "GND_5") (pintype "passive"))
      (node (ref "X17") (pin "7") (pinfunction "GND_7") (pintype "passive"))
      (node (ref "X17") (pin "8") (pinfunction "GND_8") (pintype "passive"))
      (node (ref "X18") (pin "2") (pinfunction "GND_2") (pintype "passive"))
      (node (ref "X18") (pin "3") (pinfunction "GND_3") (pintype "passive"))
      (node (ref "X18") (pin "6") (pinfunction "GND_6") (pintype "passive"))
      (node (ref "X18") (pin "8") (pinfunction "GND_8") (pintype "passive"))
      (node (ref "X19") (pin "1") (pinfunction "GND_1") (pintype "passive"))
      (node (ref "X19") (pin "10") (pinfunction "GND_10") (pintype "passive"))
      (node (ref "X19") (pin "12") (pinfunction "GND_12") (pintype "passive"))
      (node (ref "X19") (pin "13") (pinfunction "GND_13") (pintype "passive"))
      (node (ref "X19") (pin "14") (pinfunction "GND_14") (pintype "passive"))
      (node (ref "X19") (pin "3") (pinfunction "GND_3") (pintype "passive"))
      (node (ref "X19") (pin "4") (pinfunction "GND_4") (pintype "passive"))
      (node (ref "X19") (pin "5") (pinfunction "GND_5") (pintype "passive"))
      (node (ref "X19") (pin "7") (pinfunction "GND_7") (pintype "passive"))
      (node (ref "X19") (pin "8") (pinfunction "GND_8") (pintype "passive"))
      (node (ref "X2") (pin "2") (pinfunction "GND_2") (pintype "passive"))
      (node (ref "X2") (pin "3") (pinfunction "GND_3") (pintype "passive"))
      (node (ref "X2") (pin "6") (pinfunction "GND_6") (pintype "passive"))
      (node (ref "X2") (pin "8") (pinfunction "GND_8") (pintype "passive"))
      (node (ref "X20") (pin "2") (pinfunction "GND_2") (pintype "passive"))
      (node (ref "X20") (pin "3") (pinfunction "GND_3") (pintype "passive"))
      (node (ref "X20") (pin "5") (pinfunction "GND_5") (pintype "passive"))
      (node (ref "X20") (pin "7") (pinfunction "GND_7") (pintype "passive"))
      (node (ref "X20") (pin "8") (pinfunction "GND_8") (pintype "passive"))
      (node (ref "X21") (pin "2") (pinfunction "GND_2") (pintype "passive"))
      (node (ref "X21") (pin "3") (pinfunction "GND_3") (pintype "passive"))
      (node (ref "X21") (pin "6") (pinfunction "GND_6") (pintype "passive"))
      (node (ref "X21") (pin "8") (pinfunction "GND_8") (pintype "passive"))
      (node (ref "X23") (pin "10") (pinfunction "GND_10") (pintype "passive"))
      (node (ref "X23") (pin "11") (pinfunction "GND_11") (pintype "passive"))
      (node (ref "X23") (pin "12") (pinfunction "GND_12") (pintype "passive"))
      (node (ref "X23") (pin "2") (pinfunction "GND_2") (pintype "passive"))
      (node (ref "X23") (pin "3") (pinfunction "GND_3") (pintype "passive"))
      (node (ref "X23") (pin "4") (pinfunction "GND_4") (pintype "passive"))
      (node (ref "X23") (pin "5") (pinfunction "GND_5") (pintype "passive"))
      (node (ref "X23") (pin "6") (pinfunction "GND_6") (pintype "passive"))
      (node (ref "X23") (pin "7") (pinfunction "GND_7") (pintype "passive"))
      (node (ref "X23") (pin "9") (pinfunction "GND_9") (pintype "passive"))
      (node (ref "X24") (pin "10") (pinfunction "GND_10") (pintype "passive"))
      (node (ref "X24") (pin "11") (pinfunction "GND_11") (pintype "passive"))
      (node (ref "X24") (pin "12") (pinfunction "GND_12") (pintype "passive"))
      (node (ref "X24") (pin "2") (pinfunction "GND_2") (pintype "passive"))
      (node (ref "X24") (pin "3") (pinfunction "GND_3") (pintype "passive"))
      (node (ref "X24") (pin "4") (pinfunction "GND_4") (pintype "passive"))
      (node (ref "X24") (pin "5") (pinfunction "GND_5") (pintype "passive"))
      (node (ref "X24") (pin "6") (pinfunction "GND_6") (pintype "passive"))
      (node (ref "X24") (pin "7") (pinfunction "GND_7") (pintype "passive"))
      (node (ref "X24") (pin "9") (pinfunction "GND_9") (pintype "passive"))
      (node (ref "X25") (pin "4") (pinfunction "GND_4") (pintype "passive"))
      (node (ref "X25") (pin "5") (pinfunction "GND_5") (pintype "passive"))
      (node (ref "X25") (pin "6") (pinfunction "GND_6") (pintype "passive"))
      (node (ref "X26") (pin "10") (pinfunction "GND_10") (pintype "passive"))
      (node (ref "X26") (pin "11") (pinfunction "GND_11") (pintype "passive"))
      (node (ref "X26") (pin "12") (pinfunction "GND_12") (pintype "passive"))
      (node (ref "X26") (pin "2") (pinfunction "GND_2") (pintype "passive"))
      (node (ref "X26") (pin "3") (pinfunction "GND_3") (pintype "passive"))
      (node (ref "X26") (pin "4") (pinfunction "GND_4") (pintype "passive"))
      (node (ref "X26") (pin "5") (pinfunction "GND_5") (pintype "passive"))
      (node (ref "X26") (pin "6") (pinfunction "GND_6") (pintype "passive"))
      (node (ref "X26") (pin "7") (pinfunction "GND_7") (pintype "passive"))
      (node (ref "X26") (pin "9") (pinfunction "GND_9") (pintype "passive"))
      (node (ref "X27") (pin "4") (pinfunction "GND_4") (pintype "passive"))
      (node (ref "X27") (pin "5") (pinfunction "GND_5") (pintype "passive"))
      (node (ref "X27") (pin "6") (pinfunction "GND_6") (pintype "passive"))
      (node (ref "X28") (pin "4") (pinfunction "GND_4") (pintype "passive"))
      (node (ref "X28") (pin "5") (pinfunction "GND_5") (pintype "passive"))
      (node (ref "X28") (pin "6") (pinfunction "GND_6") (pintype "passive"))
      (node (ref "X3") (pin "1") (pinfunction "GND_1") (pintype "passive"))
      (node (ref "X3") (pin "10") (pinfunction "GND_10") (pintype "passive"))
      (node (ref "X3") (pin "12") (pinfunction "GND_12") (pintype "passive"))
      (node (ref "X3") (pin "13") (pinfunction "GND_13") (pintype "passive"))
      (node (ref "X3") (pin "14") (pinfunction "GND_14") (pintype "passive"))
      (node (ref "X3") (pin "3") (pinfunction "GND_3") (pintype "passive"))
      (node (ref "X3") (pin "4") (pinfunction "GND_4") (pintype "passive"))
      (node (ref "X3") (pin "5") (pinfunction "GND_5") (pintype "passive"))
      (node (ref "X3") (pin "7") (pinfunction "GND_7") (pintype "passive"))
      (node (ref "X3") (pin "8") (pinfunction "GND_8") (pintype "passive"))
      (node (ref "X4") (pin "2") (pinfunction "GND_2") (pintype "passive"))
      (node (ref "X4") (pin "3") (pinfunction "GND_3") (pintype "passive"))
      (node (ref "X4") (pin "6") (pinfunction "GND_6") (pintype "passive"))
      (node (ref "X4") (pin "8") (pinfunction "GND_8") (pintype "passive"))
      (node (ref "X5") (pin "11") (pinfunction "GND_11") (pintype "passive"))
      (node (ref "X5") (pin "16") (pinfunction "GND_16") (pintype "passive"))
      (node (ref "X5") (pin "24") (pinfunction "GND_24") (pintype "passive"))
      (node (ref "X5") (pin "29") (pinfunction "GND_29") (pintype "passive"))
      (node (ref "X5") (pin "34") (pinfunction "GND_34") (pintype "passive"))
      (node (ref "X5") (pin "38") (pinfunction "GND_38") (pintype "passive"))
      (node (ref "X5") (pin "39") (pinfunction "GND_39") (pintype "passive"))
      (node (ref "X5") (pin "6") (pinfunction "GND_6") (pintype "passive"))
      (node (ref "X6") (pin "11") (pinfunction "GND_11") (pintype "passive"))
      (node (ref "X6") (pin "16") (pinfunction "GND_16") (pintype "passive"))
      (node (ref "X6") (pin "24") (pinfunction "GND_24") (pintype "passive"))
      (node (ref "X6") (pin "29") (pinfunction "GND_29") (pintype "passive"))
      (node (ref "X6") (pin "34") (pinfunction "GND_34") (pintype "passive"))
      (node (ref "X6") (pin "38") (pinfunction "GND_38") (pintype "passive"))
      (node (ref "X6") (pin "39") (pinfunction "GND_39") (pintype "passive"))
      (node (ref "X6") (pin "6") (pinfunction "GND_6") (pintype "passive"))
      (node (ref "X7") (pin "2") (pinfunction "GND_2") (pintype "passive"))
      (node (ref "X7") (pin "3") (pinfunction "GND_3") (pintype "passive"))
      (node (ref "X7") (pin "6") (pinfunction "GND_6") (pintype "passive"))
      (node (ref "X7") (pin "8") (pinfunction "GND_8") (pintype "passive"))
      (node (ref "X8") (pin "2") (pinfunction "GND_2") (pintype "passive"))
      (node (ref "X8") (pin "3") (pinfunction "GND_3") (pintype "passive"))
      (node (ref "X8") (pin "5") (pinfunction "GND_5") (pintype "passive"))
      (node (ref "X8") (pin "7") (pinfunction "GND_7") (pintype "passive"))
      (node (ref "X8") (pin "8") (pinfunction "GND_8") (pintype "passive"))
      (node (ref "X9") (pin "2") (pinfunction "GND_2") (pintype "passive"))
      (node (ref "X9") (pin "3") (pinfunction "GND_3") (pintype "passive"))
      (node (ref "X9") (pin "6") (pinfunction "GND_6") (pintype "passive"))
      (node (ref "X9") (pin "8") (pinfunction "GND_8") (pintype "passive"))
    )
    (net (code "84") (name "Net-(P2-Pad1)") (class "Default")
      (node (ref "P2") (pin "1") (pinfunction "1_1") (pintype "passive"))
      (node (ref "REL1") (pin "2") (pinfunction "2_2") (pintype "passive"))
    )
    (net (code "85") (name "Net-(P4-Pad2)") (class "Default")
      (node (ref "P4") (pin "2") (pinfunction "2_2") (pintype "passive"))
      (node (ref "REL1") (pin "4") (pinfunction "4_4") (pintype "passive"))
      (node (ref "REL1") (pin "7") (pinfunction "7_7") (pintype "passive"))
    )
    (net (code "86") (name "Net-(R1-Pad2)") (class "Default")
      (node (ref "R1") (pin "2") (pinfunction "2_2") (pintype "passive"))
      (node (ref "REL1") (pin "8") (pinfunction "8_8") (pintype "passive"))
    )
    (net (code "87") (name "Net-(R3-Pad1)") (class "Default")
      (node (ref "R3") (pin "1") (pinfunction "1_1") (pintype "passive"))
      (node (ref "REL3") (pin "8") (pinfunction "8_8") (pintype "passive"))
    )
    (net (code "88") (name "Net-(R5-Pad1)") (class "Default")
      (node (ref "R5") (pin "1") (pinfunction "1_1") (pintype "passive"))
      (node (ref "REL4") (pin "8") (pinfunction "8_8") (pintype "passive"))
    )
    (net (code "89") (name "Net-(R7-Pad1)") (class "Default")
      (node (ref "R7") (pin "1") (pinfunction "1_1") (pintype "passive"))
      (node (ref "REL5") (pin "8") (pinfunction "8_8") (pintype "passive"))
    )
    (net (code "90") (name "Net-(VT1-К)") (class "Default")
      (node (ref "R1") (pin "1") (pinfunction "1_1") (pintype "passive"))
      (node (ref "VT1") (pin "2") (pinfunction "К_2") (pintype "passive"))
    )
    (net (code "91") (name "Net-(VT3-К)") (class "Default")
      (node (ref "R3") (pin "2") (pinfunction "2_2") (pintype "passive"))
      (node (ref "VT3") (pin "2") (pinfunction "К_2") (pintype "passive"))
    )
    (net (code "92") (name "Net-(VT4-D)") (class "Default")
      (node (ref "P7") (pin "2") (pinfunction "2_2") (pintype "passive"))
      (node (ref "REL3") (pin "3") (pinfunction "3_3") (pintype "passive"))
      (node (ref "VT4") (pin "3") (pinfunction "D_3") (pintype "passive"))
      (node (ref "X23") (pin "8") (pinfunction "OUT_8") (pintype "passive"))
    )
    (net (code "93") (name "Net-(VT4-G)") (class "Default")
      (node (ref "R4") (pin "2") (pinfunction "2_2") (pintype "passive"))
      (node (ref "VT4") (pin "1") (pinfunction "G_1") (pintype "passive"))
    )
    (net (code "94") (name "Net-(VT5-К)") (class "Default")
      (node (ref "R5") (pin "2") (pinfunction "2_2") (pintype "passive"))
      (node (ref "VT5") (pin "2") (pinfunction "К_2") (pintype "passive"))
    )
    (net (code "95") (name "Net-(VT6-D)") (class "Default")
      (node (ref "P10") (pin "2") (pinfunction "2_2") (pintype "passive"))
      (node (ref "REL4") (pin "3") (pinfunction "3_3") (pintype "passive"))
      (node (ref "VT6") (pin "3") (pinfunction "D_3") (pintype "passive"))
      (node (ref "X24") (pin "8") (pinfunction "OUT_8") (pintype "passive"))
    )
    (net (code "96") (name "Net-(VT6-G)") (class "Default")
      (node (ref "R6") (pin "2") (pinfunction "2_2") (pintype "passive"))
      (node (ref "VT6") (pin "1") (pinfunction "G_1") (pintype "passive"))
    )
    (net (code "97") (name "Net-(VT7-К)") (class "Default")
      (node (ref "R7") (pin "2") (pinfunction "2_2") (pintype "passive"))
      (node (ref "VT7") (pin "2") (pinfunction "К_2") (pintype "passive"))
    )
    (net (code "98") (name "Net-(VT8-D)") (class "Default")
      (node (ref "P11") (pin "2") (pinfunction "2_2") (pintype "passive"))
      (node (ref "REL5") (pin "3") (pinfunction "3_3") (pintype "passive"))
      (node (ref "VT8") (pin "3") (pinfunction "D_3") (pintype "passive"))
      (node (ref "X26") (pin "8") (pinfunction "OUT_8") (pintype "passive"))
    )
    (net (code "99") (name "Net-(VT8-G)") (class "Default")
      (node (ref "R8") (pin "2") (pinfunction "2_2") (pintype "passive"))
      (node (ref "VT8") (pin "1") (pinfunction "G_1") (pintype "passive"))
    )
    (net (code "100") (name "unconnected-(REL3-Pad2)") (class "Default")
      (node (ref "REL3") (pin "2") (pinfunction "2_2") (pintype "passive"))
    )
    (net (code "101") (name "unconnected-(REL3-Pad7)") (class "Default")
      (node (ref "REL3") (pin "7") (pinfunction "7_7") (pintype "passive"))
    )
    (net (code "102") (name "unconnected-(REL4-Pad2)") (class "Default")
      (node (ref "REL4") (pin "2") (pinfunction "2_2") (pintype "passive"))
    )
    (net (code "103") (name "unconnected-(REL4-Pad7)") (class "Default")
      (node (ref "REL4") (pin "7") (pinfunction "7_7") (pintype "passive"))
    )
    (net (code "104") (name "unconnected-(REL5-Pad2)") (class "Default")
      (node (ref "REL5") (pin "2") (pinfunction "2_2") (pintype "passive"))
    )
    (net (code "105") (name "unconnected-(REL5-Pad7)") (class "Default")
      (node (ref "REL5") (pin "7") (pinfunction "7_7") (pintype "passive"))
    )
    (net (code "106") (name "unconnected-(X5-NC-Pad1)") (class "Default")
      (node (ref "X5") (pin "1") (pinfunction "NC_1") (pintype "passive"))
    )
    (net (code "107") (name "unconnected-(X5-NC-Pad18)") (class "Default")
      (node (ref "X5") (pin "18") (pinfunction "NC_18") (pintype "passive"))
    )
    (net (code "108") (name "unconnected-(X5-NC-Pad19)") (class "Default")
      (node (ref "X5") (pin "19") (pinfunction "NC_19") (pintype "passive"))
    )
    (net (code "109") (name "unconnected-(X5-NC-Pad37)") (class "Default")
      (node (ref "X5") (pin "37") (pinfunction "NC_37") (pintype "passive"))
    )
    (net (code "110") (name "unconnected-(X5-P1.7-Pad25)") (class "Default")
      (node (ref "X5") (pin "25") (pinfunction "P1.7_25") (pintype "passive"))
    )
    (net (code "111") (name "unconnected-(X5-PFI2-Pad17)") (class "Default")
      (node (ref "X5") (pin "17") (pinfunction "PFI2_17") (pintype "passive"))
    )
    (net (code "112") (name "unconnected-(X5-PFI3-Pad35)") (class "Default")
      (node (ref "X5") (pin "35") (pinfunction "PFI3_35") (pintype "passive"))
    )
    (net (code "113") (name "unconnected-(X6-NC-Pad1)") (class "Default")
      (node (ref "X6") (pin "1") (pinfunction "NC_1") (pintype "passive"))
    )
    (net (code "114") (name "unconnected-(X6-NC-Pad18)") (class "Default")
      (node (ref "X6") (pin "18") (pinfunction "NC_18") (pintype "passive"))
    )
    (net (code "115") (name "unconnected-(X6-NC-Pad19)") (class "Default")
      (node (ref "X6") (pin "19") (pinfunction "NC_19") (pintype "passive"))
    )
    (net (code "116") (name "unconnected-(X6-NC-Pad37)") (class "Default")
      (node (ref "X6") (pin "37") (pinfunction "NC_37") (pintype "passive"))
    )
    (net (code "117") (name "unconnected-(X6-P1.1-Pad28)") (class "Default")
      (node (ref "X6") (pin "28") (pinfunction "P1.1_28") (pintype "passive"))
    )
    (net (code "118") (name "unconnected-(X6-P1.2-Pad9)") (class "Default")
      (node (ref "X6") (pin "9") (pinfunction "P1.2_9") (pintype "passive"))
    )
    (net (code "119") (name "unconnected-(X6-P1.3-Pad27)") (class "Default")
      (node (ref "X6") (pin "27") (pinfunction "P1.3_27") (pintype "passive"))
    )
    (net (code "120") (name "unconnected-(X6-P1.7-Pad25)") (class "Default")
      (node (ref "X6") (pin "25") (pinfunction "P1.7_25") (pintype "passive"))
    )
    (net (code "121") (name "unconnected-(X6-P2.0-Pad5)") (class "Default")
      (node (ref "X6") (pin "5") (pinfunction "P2.0_5") (pintype "passive"))
    )
    (net (code "122") (name "unconnected-(X6-P2.1-Pad23)") (class "Default")
      (node (ref "X6") (pin "23") (pinfunction "P2.1_23") (pintype "passive"))
    )
    (net (code "123") (name "unconnected-(X6-P2.2-Pad4)") (class "Default")
      (node (ref "X6") (pin "4") (pinfunction "P2.2_4") (pintype "passive"))
    )
    (net (code "124") (name "unconnected-(X6-P2.3-Pad22)") (class "Default")
      (node (ref "X6") (pin "22") (pinfunction "P2.3_22") (pintype "passive"))
    )
    (net (code "125") (name "unconnected-(X6-P2.4-Pad3)") (class "Default")
      (node (ref "X6") (pin "3") (pinfunction "P2.4_3") (pintype "passive"))
    )
    (net (code "126") (name "unconnected-(X6-P2.5-Pad21)") (class "Default")
      (node (ref "X6") (pin "21") (pinfunction "P2.5_21") (pintype "passive"))
    )
    (net (code "127") (name "unconnected-(X6-P2.6-Pad2)") (class "Default")
      (node (ref "X6") (pin "2") (pinfunction "P2.6_2") (pintype "passive"))
    )
    (net (code "128") (name "unconnected-(X6-P2.7-Pad20)") (class "Default")
      (node (ref "X6") (pin "20") (pinfunction "P2.7_20") (pintype "passive"))
    )
    (net (code "129") (name "unconnected-(X6-PFI1-Pad36)") (class "Default")
      (node (ref "X6") (pin "36") (pinfunction "PFI1_36") (pintype "passive"))
    )
    (net (code "130") (name "unconnected-(X6-PFI2-Pad17)") (class "Default")
      (node (ref "X6") (pin "17") (pinfunction "PFI2_17") (pintype "passive"))
    )
    (net (code "131") (name "unconnected-(X6-PFI3-Pad35)") (class "Default")
      (node (ref "X6") (pin "35") (pinfunction "PFI3_35") (pintype "passive"))
    )
    (net (code "132") (name "unconnected-(X22-+V-Pad3)") (class "Default")
      (node (ref "X22") (pin "3") (pinfunction "+V_3") (pintype "passive"))
    )
    (net (code "133") (name "unconnected-(X27-2-Pad3)") (class "Default")
      (node (ref "X27") (pin "3") (pinfunction "2_3") (pintype "passive"))
    )
  )
)
